# basic_ftdi.net
KiCad netlist of a schematic drawn in EAGLE
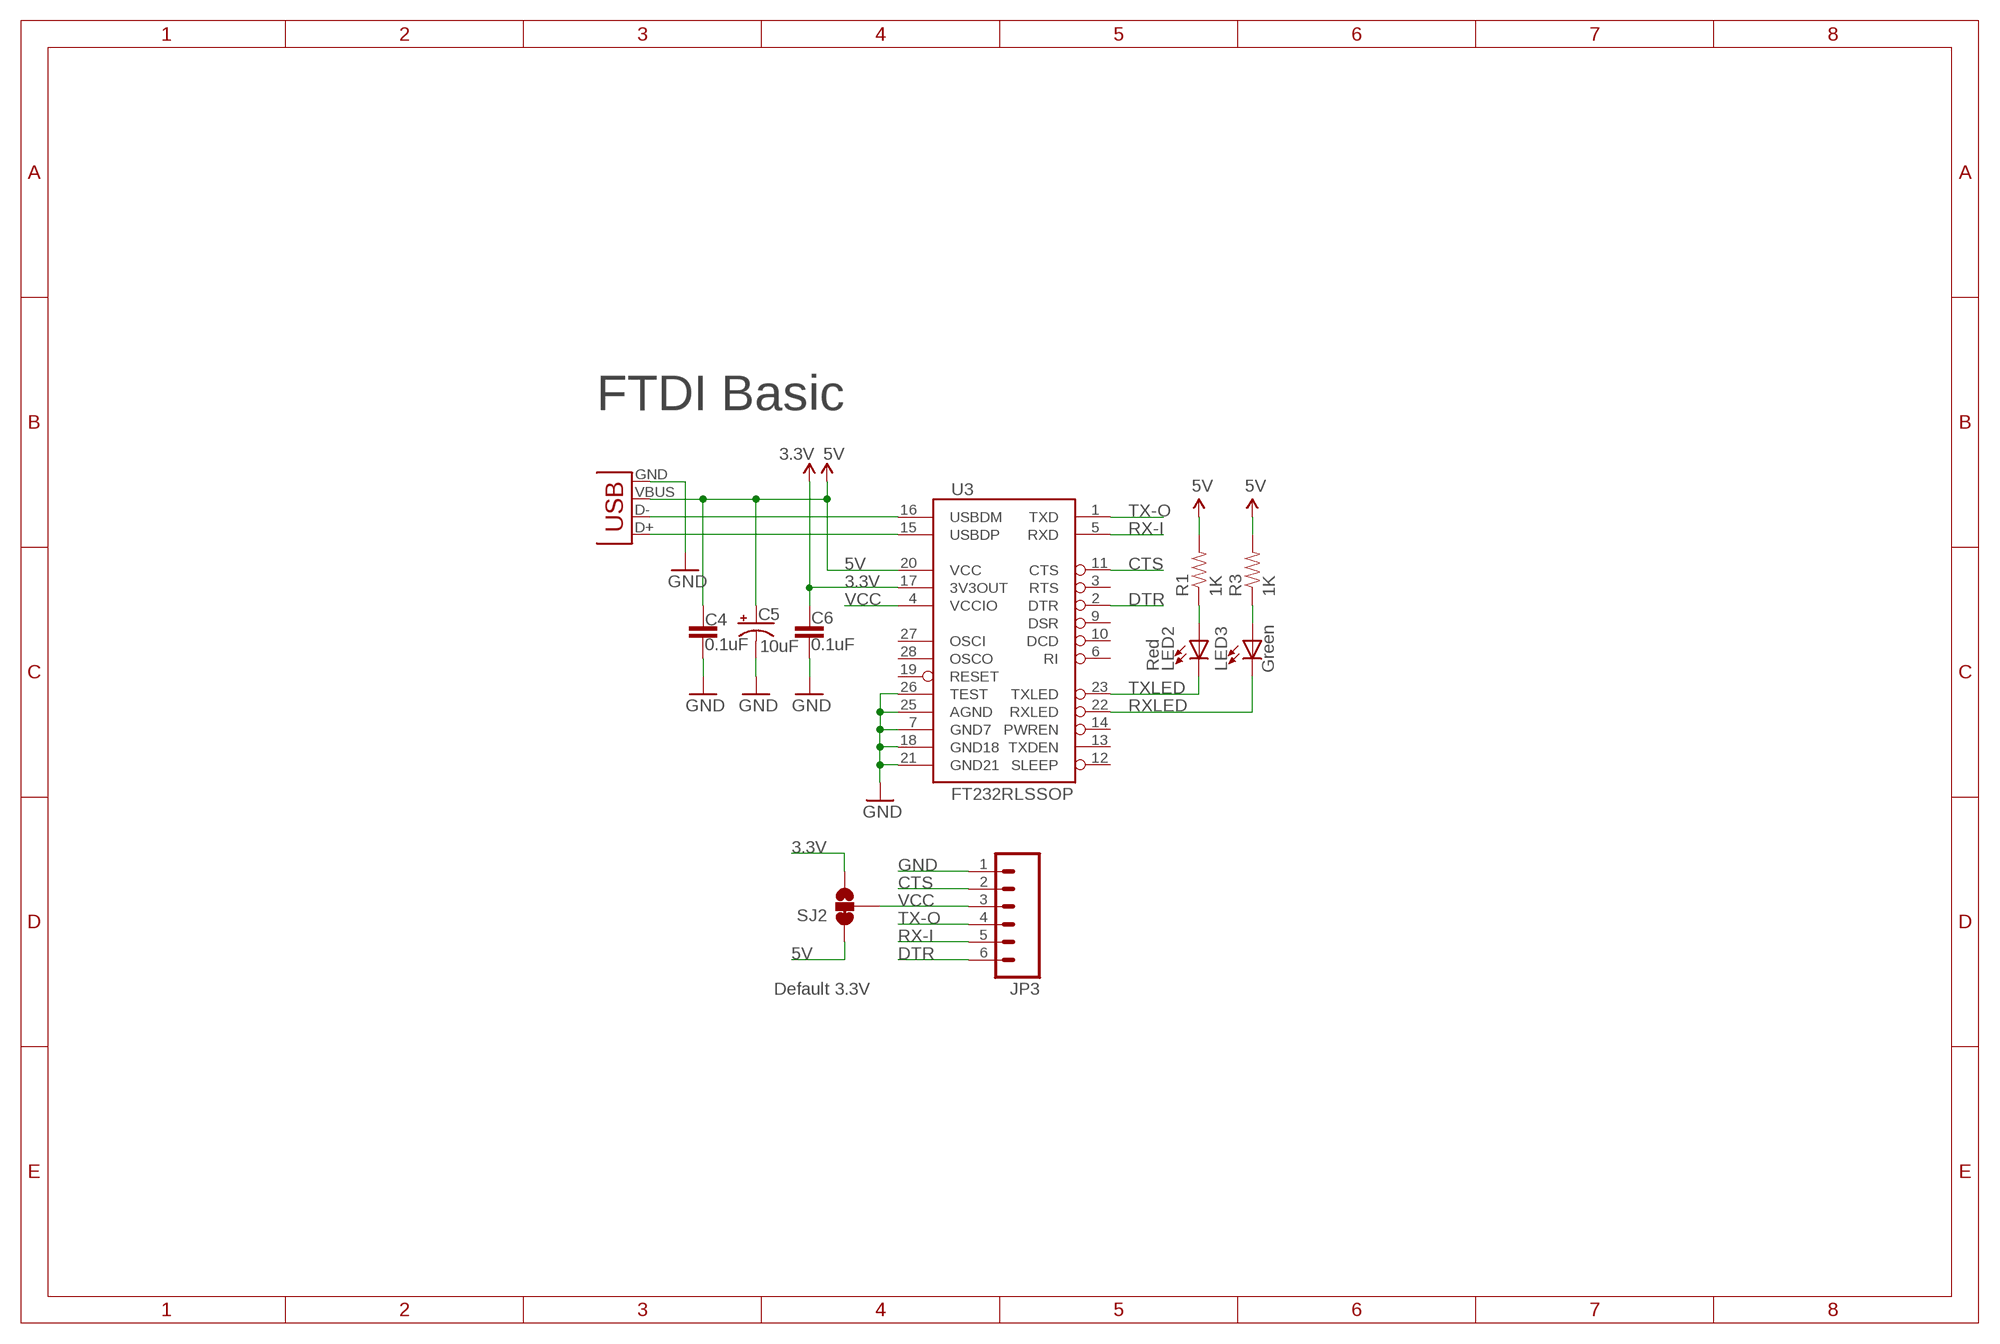
[diagram p0: schematic, sheet 1]

(export (version "E")
  (design (tool "Eeschema 10.0.6"))
  (components
    (comp (ref "C4")
      (value "0.1uF")
      (footprint "eagle-import:0402-CAP")
      (libsource (lib "eagle-import") (part "CAP0402-CAP"))
    )
    (comp (ref "C5")
      (value "10uF")
      (footprint "eagle-import:EIA3216")
      (libsource (lib "eagle-import") (part "CAP_POL1206"))
    )
    (comp (ref "C6")
      (value "0.1uF")
      (footprint "eagle-import:0402-CAP")
      (libsource (lib "eagle-import") (part "CAP0402-CAP"))
    )
    (comp (ref "JP3")
      (value "M06SIP")
      (footprint "eagle-import:1X06")
      (libsource (lib "eagle-import") (part "M06SIP"))
    )
    (comp (ref "LED2")
      (value "Red")
      (footprint "eagle-import:LED-0603")
      (libsource (lib "eagle-import") (part "LED0603"))
    )
    (comp (ref "LED3")
      (value "Green")
      (footprint "eagle-import:LED-0603")
      (libsource (lib "eagle-import") (part "LED0603"))
    )
    (comp (ref "R1")
      (value "1K")
      (footprint "eagle-import:0402-RES")
      (libsource (lib "eagle-import") (part "RESISTOR0402-RES"))
    )
    (comp (ref "R3")
      (value "1K")
      (footprint "eagle-import:0402-RES")
      (libsource (lib "eagle-import") (part "RESISTOR0402-RES"))
    )
    (comp (ref "SJ2")
      (value "SOLDERJUMPER_2WAYS")
      (footprint "eagle-import:SJ_3")
      (libsource (lib "eagle-import") (part "SOLDERJUMPER_2WAYS"))
    )
    (comp (ref "U3")
      (value "FT232RLSSOP")
      (footprint "eagle-import:SSOP28DB")
      (libsource (lib "eagle-import") (part "FT232RLSSOP"))
    )
    (comp (ref "X2")
      (value "USB-SMD-NS")
      (footprint "eagle-import:USB-MINIB-NOSTOP")
      (libsource (lib "eagle-import") (part "USB-SMD-NS"))
    )
  )
  (nets
    (net (code "1") (name "/CTS") (class "Default")
      (node (ref "JP3") (pin "2") (pinfunction "2_2") (pintype "passive"))
      (node (ref "U3") (pin "11") (pinfunction "CTS_11") (pintype "input"))
    )
    (net (code "2") (name "/DTR") (class "Default")
      (node (ref "JP3") (pin "6") (pinfunction "6_6") (pintype "passive"))
      (node (ref "U3") (pin "2") (pinfunction "DTR_2") (pintype "output"))
    )
    (net (code "3") (name "/RX-I") (class "Default")
      (node (ref "JP3") (pin "5") (pinfunction "5_5") (pintype "passive"))
      (node (ref "U3") (pin "5") (pinfunction "RXD_5") (pintype "input"))
    )
    (net (code "4") (name "/RXLED") (class "Default")
      (node (ref "LED3") (pin "C") (pinfunction "C_C") (pintype "passive"))
      (node (ref "U3") (pin "22") (pinfunction "RXLED_22") (pintype "input"))
    )
    (net (code "5") (name "/TX-O") (class "Default")
      (node (ref "JP3") (pin "4") (pinfunction "4_4") (pintype "passive"))
      (node (ref "U3") (pin "1") (pinfunction "TXD_1") (pintype "output"))
    )
    (net (code "6") (name "/TXLED") (class "Default")
      (node (ref "LED2") (pin "C") (pinfunction "C_C") (pintype "passive"))
      (node (ref "U3") (pin "23") (pinfunction "TXLED_23") (pintype "input"))
    )
    (net (code "7") (name "/VCC") (class "Default")
      (node (ref "JP3") (pin "3") (pinfunction "3_3") (pintype "passive"))
      (node (ref "SJ2") (pin "2") (pinfunction "2_2") (pintype "passive"))
      (node (ref "U3") (pin "4") (pinfunction "VCCIO_4") (pintype "power_in"))
    )
    (net (code "8") (name "3.3V") (class "Default")
      (node (ref "C6") (pin "1") (pinfunction "1_1") (pintype "passive"))
      (node (ref "SJ2") (pin "3") (pinfunction "3_3") (pintype "passive"))
      (node (ref "U3") (pin "17") (pinfunction "3V3OUT_17") (pintype "output"))
    )
    (net (code "9") (name "5V") (class "Default")
      (node (ref "C4") (pin "1") (pinfunction "1_1") (pintype "passive"))
      (node (ref "C5") (pin "A") (pinfunction "+_A") (pintype "passive"))
      (node (ref "R1") (pin "2") (pinfunction "2_2") (pintype "passive"))
      (node (ref "R3") (pin "2") (pinfunction "2_2") (pintype "passive"))
      (node (ref "SJ2") (pin "1") (pinfunction "1_1") (pintype "passive"))
      (node (ref "U3") (pin "20") (pinfunction "VCC_20") (pintype "power_in"))
      (node (ref "X2") (pin "VBUS") (pinfunction "VBUS_VBUS") (pintype "bidirectional"))
    )
    (net (code "10") (name "GND") (class "Default")
      (node (ref "C4") (pin "2") (pinfunction "2_2") (pintype "passive"))
      (node (ref "C5") (pin "C") (pinfunction "-_C") (pintype "passive"))
      (node (ref "C6") (pin "2") (pinfunction "2_2") (pintype "passive"))
      (node (ref "JP3") (pin "1") (pinfunction "1_1") (pintype "passive"))
      (node (ref "U3") (pin "18") (pinfunction "GND18_18") (pintype "power_in"))
      (node (ref "U3") (pin "21") (pinfunction "GND21_21") (pintype "power_in"))
      (node (ref "U3") (pin "25") (pinfunction "AGND_25") (pintype "power_in"))
      (node (ref "U3") (pin "26") (pinfunction "TEST_26") (pintype "input"))
      (node (ref "U3") (pin "7") (pinfunction "GND7_7") (pintype "power_in"))
      (node (ref "X2") (pin "GND") (pinfunction "GND_GND") (pintype "bidirectional"))
    )
    (net (code "11") (name "Net-(LED2-PadA)") (class "Default")
      (node (ref "LED2") (pin "A") (pinfunction "A_A") (pintype "passive"))
      (node (ref "R1") (pin "1") (pinfunction "1_1") (pintype "passive"))
    )
    (net (code "12") (name "Net-(LED3-PadA)") (class "Default")
      (node (ref "LED3") (pin "A") (pinfunction "A_A") (pintype "passive"))
      (node (ref "R3") (pin "1") (pinfunction "1_1") (pintype "passive"))
    )
    (net (code "13") (name "Net-(U3-USBDM)") (class "Default")
      (node (ref "U3") (pin "16") (pinfunction "USBDM_16") (pintype "bidirectional"))
      (node (ref "X2") (pin "D-") (pinfunction "D-_D-") (pintype "bidirectional"))
    )
    (net (code "14") (name "Net-(U3-USBDP)") (class "Default")
      (node (ref "U3") (pin "15") (pinfunction "USBDP_15") (pintype "bidirectional"))
      (node (ref "X2") (pin "D+") (pinfunction "D+_D+") (pintype "bidirectional"))
    )
    (net (code "15") (name "unconnected-(U3-DCD-Pad10)") (class "Default")
      (node (ref "U3") (pin "10") (pinfunction "DCD_10") (pintype "input"))
    )
    (net (code "16") (name "unconnected-(U3-DSR-Pad9)") (class "Default")
      (node (ref "U3") (pin "9") (pinfunction "DSR_9") (pintype "input"))
    )
    (net (code "17") (name "unconnected-(U3-OSCI-Pad27)") (class "Default")
      (node (ref "U3") (pin "27") (pinfunction "OSCI_27") (pintype "input"))
    )
    (net (code "18") (name "unconnected-(U3-OSCO-Pad28)") (class "Default")
      (node (ref "U3") (pin "28") (pinfunction "OSCO_28") (pintype "output"))
    )
    (net (code "19") (name "unconnected-(U3-PWREN-Pad14)") (class "Default")
      (node (ref "U3") (pin "14") (pinfunction "PWREN_14") (pintype "input"))
    )
    (net (code "20") (name "unconnected-(U3-RESET-Pad19)") (class "Default")
      (node (ref "U3") (pin "19") (pinfunction "RESET_19") (pintype "input"))
    )
    (net (code "21") (name "unconnected-(U3-RI-Pad6)") (class "Default")
      (node (ref "U3") (pin "6") (pinfunction "RI_6") (pintype "input"))
    )
    (net (code "22") (name "unconnected-(U3-RTS-Pad3)") (class "Default")
      (node (ref "U3") (pin "3") (pinfunction "RTS_3") (pintype "output"))
    )
    (net (code "23") (name "unconnected-(U3-SLEEP-Pad12)") (class "Default")
      (node (ref "U3") (pin "12") (pinfunction "SLEEP_12") (pintype "input"))
    )
    (net (code "24") (name "unconnected-(U3-TXDEN-Pad13)") (class "Default")
      (node (ref "U3") (pin "13") (pinfunction "TXDEN_13") (pintype "input"))
    )
  )
)
